# SS.net
KiCad netlist of a schematic drawn in Altium Designer
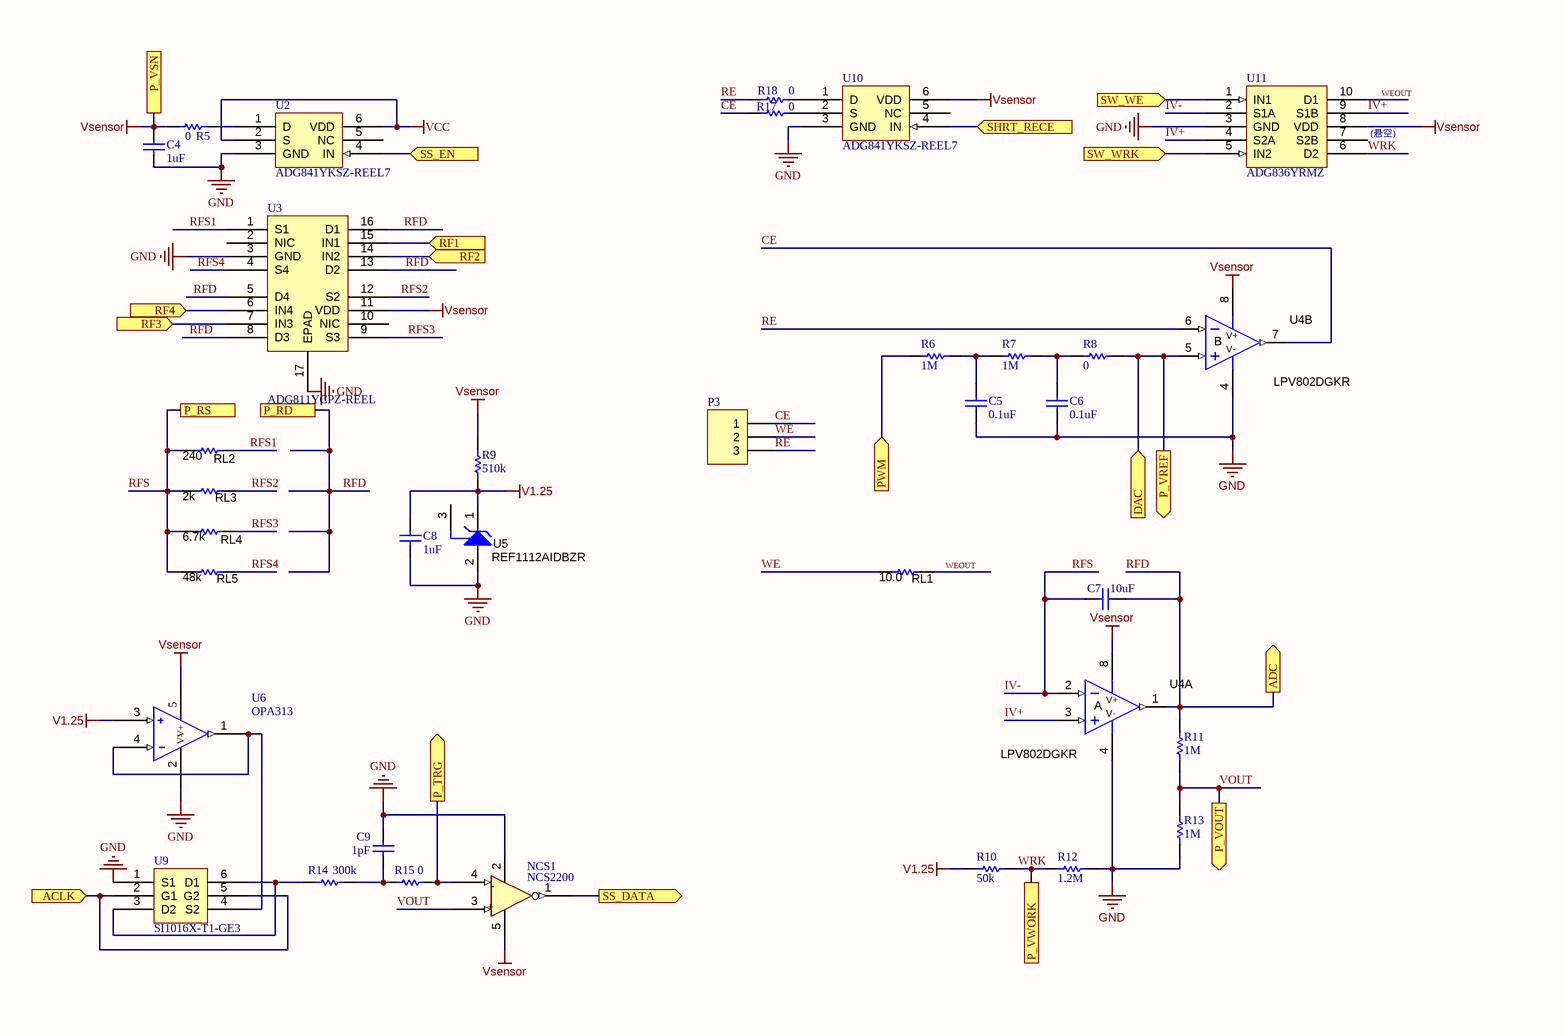
[diagram p0: SS.SchDoc]

(export (version "E")
  (design (tool "Eeschema 10.0.6"))
  (components
    (comp (ref "C4")
      (value "1uF")
      (footprint "0402")
      (description "Ceramic Capacitor (Surface Mount)")
      (fields (field (name "MANUFACTURER") "Generic Ceramic Chip Cap (TBD)"))
      (libsource (lib "Sensor") (part "Cap"))
    )
    (comp (ref "C5")
      (value "0.1uF")
      (footprint "0402")
      (description "Ceramic Capacitor (Surface Mount)")
      (fields (field (name "MANUFACTURER") "Generic Ceramic Chip Cap (TBD)"))
      (libsource (lib "Sensor") (part "Cap"))
    )
    (comp (ref "C6")
      (value "0.1uF")
      (footprint "0402")
      (description "Ceramic Capacitor (Surface Mount)")
      (fields (field (name "MANUFACTURER") "Generic Ceramic Chip Cap (TBD)"))
      (libsource (lib "Sensor") (part "Cap"))
    )
    (comp (ref "C7")
      (value "10uF")
      (footprint "0402")
      (description "Ceramic Capacitor (Surface Mount)")
      (fields (field (name "MANUFACTURER") "Generic Ceramic Chip Cap (TBD)"))
      (libsource (lib "Sensor") (part "Cap"))
    )
    (comp (ref "C8")
      (value "1uF")
      (footprint "0402")
      (description "Ceramic Capacitor (Surface Mount)")
      (fields (field (name "MANUFACTURER") "Generic Ceramic Chip Cap (TBD)"))
      (libsource (lib "Sensor") (part "Cap"))
    )
    (comp (ref "C9")
      (value "1pF")
      (footprint "0805")
      (description "Ceramic Capacitor (Surface Mount)")
      (fields (field (name "MANUFACTURER") "Generic Ceramic Chip Cap (TBD)"))
      (libsource (lib "Sensor") (part "Cap"))
    )
    (comp (ref "NCS1")
      (value "NCS2200")
      (footprint "SC70-5")
      (description "Comparator: On Semi 10uA Comparator")
      (fields
        (field (name "DIGI-KEY PART NUMBER") "NCS2200SQ2T2GOSTR-ND")
        (field (name "MANUFACTURER") "ON Semiconductor")
      )
      (libsource (lib "Sensor") (part "NCS2200"))
    )
    (comp (ref "P3")
      (value "~")
      (footprint "HDR1X3")
      (description "Header, 3-Pin")
      (fields (field (name "PUBLISHER") "Altium Limited"))
      (libsource (lib "Miscellaneous Connectors") (part "Header 3"))
    )
    (comp (ref "R5")
      (value "0")
      (footprint "0402")
      (description "Chip Resistor (Surface Mount)")
      (fields (field (name "MANUFACTURER") "Generic Chip Res (TBD)"))
      (libsource (lib "Sensor") (part "Res"))
    )
    (comp (ref "R6")
      (value "1M")
      (footprint "0402")
      (description "Chip Resistor (Surface Mount)")
      (fields (field (name "MANUFACTURER") "Generic Chip Res (TBD)"))
      (libsource (lib "Sensor") (part "Res"))
    )
    (comp (ref "R7")
      (value "1M")
      (footprint "0402")
      (description "Chip Resistor (Surface Mount)")
      (fields (field (name "MANUFACTURER") "Generic Chip Res (TBD)"))
      (libsource (lib "Sensor") (part "Res"))
    )
    (comp (ref "R8")
      (value "0")
      (footprint "0402")
      (description "Chip Resistor (Surface Mount)")
      (fields (field (name "MANUFACTURER") "Generic Chip Res (TBD)"))
      (libsource (lib "Sensor") (part "Res"))
    )
    (comp (ref "R9")
      (value "510k")
      (footprint "0402")
      (description "Chip Resistor (Surface Mount)")
      (fields (field (name "MANUFACTURER") "Generic Chip Res (TBD)"))
      (libsource (lib "Sensor") (part "Res"))
    )
    (comp (ref "R10")
      (value "50k")
      (footprint "0402")
      (description "Chip Resistor (Surface Mount)")
      (fields (field (name "MANUFACTURER") "Generic Chip Res (TBD)"))
      (libsource (lib "Sensor") (part "Res"))
    )
    (comp (ref "R11")
      (value "1M")
      (footprint "0402")
      (description "Chip Resistor (Surface Mount)")
      (fields (field (name "MANUFACTURER") "Generic Chip Res (TBD)"))
      (libsource (lib "Sensor") (part "Res"))
    )
    (comp (ref "R12")
      (value "1.2M")
      (footprint "0402")
      (description "Chip Resistor (Surface Mount)")
      (fields (field (name "MANUFACTURER") "Generic Chip Res (TBD)"))
      (libsource (lib "Sensor") (part "Res"))
    )
    (comp (ref "R13")
      (value "1M")
      (footprint "0402")
      (description "Chip Resistor (Surface Mount)")
      (fields (field (name "MANUFACTURER") "Generic Chip Res (TBD)"))
      (libsource (lib "Sensor") (part "Res"))
    )
    (comp (ref "R14")
      (value "300k")
      (footprint "0805")
      (description "Chip Resistor (Surface Mount)")
      (fields (field (name "MANUFACTURER") "Generic Chip Res (TBD)"))
      (libsource (lib "Sensor") (part "Res"))
    )
    (comp (ref "R15")
      (value "0")
      (footprint "0402")
      (description "Chip Resistor (Surface Mount)")
      (fields (field (name "MANUFACTURER") "Generic Chip Res (TBD)"))
      (libsource (lib "Sensor") (part "Res"))
    )
    (comp (ref "R17")
      (value "0")
      (footprint "0402")
      (description "Chip Resistor (Surface Mount)")
      (fields (field (name "MANUFACTURER") "Generic Chip Res (TBD)"))
      (libsource (lib "Sensor") (part "Res"))
    )
    (comp (ref "R18")
      (value "0")
      (footprint "0402")
      (description "Chip Resistor (Surface Mount)")
      (fields (field (name "MANUFACTURER") "Generic Chip Res (TBD)"))
      (libsource (lib "Sensor") (part "Res"))
    )
    (comp (ref "RL1")
      (value "10.0")
      (footprint "0402")
      (description "RES, 10.0, 0.1%, 0.1 W, 0402")
      (fields (field (name "Comment") "RT0402BRD0710RL"))
      (libsource (lib "Sensor") (part "RT0402BRD0710RL"))
    )
    (comp (ref "RL2")
      (value "240")
      (footprint "0402")
      (description "RES, 240, 0.1%, 0.1 W, 0402")
      (fields (field (name "Comment") "RT0402BRD07240RL"))
      (libsource (lib "Sensor") (part "RT0402BRD07240RL"))
    )
    (comp (ref "RL3")
      (value "2k")
      (footprint "0402")
      (description "RES, 2k, 0.1%, 0.1 W, 0402")
      (fields (field (name "Comment") "RT0402BRD072KL"))
      (libsource (lib "Sensor") (part "RT0402BRD072KL"))
    )
    (comp (ref "RL4")
      (value "6.7k")
      (footprint "0402")
      (description "RES, 6.7k, 0.1%, 0.1 W, 0402")
      (fields (field (name "Comment") "RT0402BRD076K7L"))
      (libsource (lib "Sensor") (part "RT0402BRD076K7L"))
    )
    (comp (ref "RL5")
      (value "48k")
      (footprint "0402")
      (description "RES, 48k, 0.1%, 0.1 W, 0402")
      (fields (field (name "Comment") "RT0402BRD0748KL"))
      (libsource (lib "Sensor") (part "RT0402BRD0748KL"))
    )
    (comp (ref "U2")
      (value "ADG841YKSZ-REEL7")
      (footprint "SOT65P210X110-6N")
      (description "单通道单刀单掷开关")
      (libsource (lib "Sensor") (part "ADG841YKSZ-REEL7"))
    )
    (comp (ref "U3")
      (value "ADG811YCPZ-REEL")
      (footprint "QFN50P300X300X90-17N")
      (description "四通道单刀单掷开关")
      (libsource (lib "9e10b744bb4c87c33691f54f9cb3eff1_25b2db50bc18869c33ddf303d90bd74c_8") (part "ADG811YCPZ-REEL"))
    )
    (comp (ref "U4")
      (value "LPV802DGKR")
      (footprint "DGK0008A_N")
      (description "350 nA Rail-to-Rail I/O Nanopower Operational Amplifier Family, DGK0008A")
      (fields
        (field (name "ALTERNATE PARTNUMBER") "LPV802DGKT")
        (field (name "MANUFACTURER") "Texas Instruments")
        (field (name "PUBLISHER") "Texas Instruments")
      )
      (libsource (lib "Sensor") (part "LPV802DGKR"))
    )
    (comp (ref "U5")
      (value "REF1112AIDBZR")
      (footprint "DBZ0003A_N")
      (fields
        (field (name "MANUFACTURER") "Texas Instruments")
        (field (name "ALTERNATE PARTNUMBER") "Equivalent")
      )
      (libsource (lib "Sensor") (part "REF1112AIDBZR"))
    )
    (comp (ref "U6")
      (value "OPA313")
      (footprint "SOT95P280X145-5N")
      (description "低功耗运算放大器")
      (libsource (lib "Sensor") (part "OPA313"))
    )
    (comp (ref "U9")
      (value "SI1016X-T1-GE3")
      (footprint "SC-89-6 Vishay")
      (description "N/P沟道增强型MOS管")
      (libsource (lib "Sensor") (part "SI1016X-T1-GE3"))
    )
    (comp (ref "U10")
      (value "ADG841YKSZ-REEL7")
      (footprint "SOT65P210X110-6N")
      (description "单通道单刀单掷开关")
      (libsource (lib "Sensor") (part "ADG841YKSZ-REEL7"))
    )
    (comp (ref "U11")
      (value "ADG836YRMZ")
      (footprint "SOP50P490X110-10N")
      (description "双通道单刀双掷开关")
      (libsource (lib "Sensor") (part "ADG836YRMZ"))
    )
  )
  (nets
    (net (code "2") (name "/ACLK") (class "Default")
      (node (ref "U9") (pin "2") (pinfunction "G1_2") (pintype "passive"))
      (node (ref "U9") (pin "5") (pinfunction "G2_5") (pintype "passive"))
    )
    (net (code "3") (name "/CE") (class "Default")
      (node (ref "P3") (pin "1") (pinfunction "1_1") (pintype "passive"))
      (node (ref "R17") (pin "2") (pinfunction "2_2") (pintype "passive"))
      (node (ref "U4") (pin "7") (pinfunction "OUT_7") (pintype "output"))
    )
    (net (code "4") (name "/DAC") (class "Default")
      (node (ref "R8") (pin "2") (pinfunction "2_2") (pintype "passive"))
      (node (ref "U4") (pin "5") (pinfunction "IN+_5") (pintype "input"))
    )
    (net (code "5") (name "/IV+") (class "Default")
      (node (ref "U11") (pin "4") (pinfunction "S2A_4") (pintype "passive"))
      (node (ref "U11") (pin "9") (pinfunction "S1B_9") (pintype "passive"))
      (node (ref "U4") (pin "3") (pinfunction "IN+_3") (pintype "input"))
    )
    (net (code "6") (name "/IV-") (class "Default")
      (node (ref "C7") (pin "2") (pinfunction "2_2") (pintype "passive"))
      (node (ref "RL2") (pin "1") (pinfunction "1_1") (pintype "passive"))
      (node (ref "RL3") (pin "1") (pinfunction "1_1") (pintype "passive"))
      (node (ref "RL4") (pin "1") (pinfunction "1_1") (pintype "passive"))
      (node (ref "RL5") (pin "1") (pinfunction "1_1") (pintype "passive"))
      (node (ref "U11") (pin "2") (pinfunction "S1A_2") (pintype "passive"))
      (node (ref "U4") (pin "2") (pinfunction "IN-_2") (pintype "input"))
    )
    (net (code "7") (name "/PWM") (class "Default")
      (node (ref "R6") (pin "2") (pinfunction "2_2") (pintype "passive"))
    )
    (net (code "8") (name "/P_TRG") (class "Default")
      (node (ref "NCS1") (pin "4") (pinfunction "In-_4") (pintype "input"))
      (node (ref "R15") (pin "1") (pinfunction "1_1") (pintype "passive"))
    )
    (net (code "9") (name "/RE") (class "Default")
      (node (ref "P3") (pin "3") (pinfunction "3_3") (pintype "passive"))
      (node (ref "R18") (pin "2") (pinfunction "2_2") (pintype "passive"))
      (node (ref "U4") (pin "6") (pinfunction "IN-_6") (pintype "input"))
    )
    (net (code "10") (name "/RF1") (class "Default")
      (node (ref "U3") (pin "15") (pinfunction "IN1_15") (pintype "passive"))
    )
    (net (code "11") (name "/RF2") (class "Default")
      (node (ref "U3") (pin "14") (pinfunction "IN2_14") (pintype "passive"))
    )
    (net (code "12") (name "/RF3") (class "Default")
      (node (ref "U3") (pin "7") (pinfunction "IN3_7") (pintype "passive"))
    )
    (net (code "13") (name "/RF4") (class "Default")
      (node (ref "U3") (pin "6") (pinfunction "IN4_6") (pintype "passive"))
    )
    (net (code "14") (name "/RFD") (class "Default")
      (node (ref "C7") (pin "1") (pinfunction "1_1") (pintype "passive"))
      (node (ref "R11") (pin "1") (pinfunction "1_1") (pintype "passive"))
      (node (ref "U3") (pin "13") (pinfunction "D2_13") (pintype "passive"))
      (node (ref "U3") (pin "16") (pinfunction "D1_16") (pintype "passive"))
      (node (ref "U3") (pin "5") (pinfunction "D4_5") (pintype "passive"))
      (node (ref "U3") (pin "8") (pinfunction "D3_8") (pintype "passive"))
      (node (ref "U4") (pin "1") (pinfunction "OUT_1") (pintype "output"))
    )
    (net (code "15") (name "/RFS1") (class "Default")
      (node (ref "RL2") (pin "2") (pinfunction "2_2") (pintype "passive"))
      (node (ref "U3") (pin "1") (pinfunction "S1_1") (pintype "passive"))
    )
    (net (code "16") (name "/RFS2") (class "Default")
      (node (ref "RL3") (pin "2") (pinfunction "2_2") (pintype "passive"))
      (node (ref "U3") (pin "12") (pinfunction "S2_12") (pintype "passive"))
    )
    (net (code "17") (name "/RFS3") (class "Default")
      (node (ref "RL4") (pin "2") (pinfunction "2_2") (pintype "passive"))
      (node (ref "U3") (pin "9") (pinfunction "S3_9") (pintype "passive"))
    )
    (net (code "18") (name "/RFS4") (class "Default")
      (node (ref "RL5") (pin "2") (pinfunction "2_2") (pintype "passive"))
      (node (ref "U3") (pin "4") (pinfunction "S4_4") (pintype "passive"))
    )
    (net (code "19") (name "/SHRT_RECE") (class "Default")
      (node (ref "U10") (pin "4") (pinfunction "IN_4") (pintype "input"))
    )
    (net (code "20") (name "/SS_DATA") (class "Default")
      (node (ref "NCS1") (pin "1") (pinfunction "OUT_1") (pintype "output"))
    )
    (net (code "21") (name "/SS_EN") (class "Default")
      (node (ref "U2") (pin "4") (pinfunction "IN_4") (pintype "input"))
    )
    (net (code "22") (name "/SW_WE") (class "Default")
      (node (ref "U11") (pin "1") (pinfunction "IN1_1") (pintype "input"))
    )
    (net (code "23") (name "/SW_WRK") (class "Default")
      (node (ref "U11") (pin "5") (pinfunction "IN2_5") (pintype "input"))
    )
    (net (code "24") (name "/VOUT") (class "Default")
      (node (ref "NCS1") (pin "3") (pinfunction "IN+_3") (pintype "input"))
      (node (ref "R11") (pin "2") (pinfunction "2_2") (pintype "passive"))
      (node (ref "R13") (pin "1") (pinfunction "1_1") (pintype "passive"))
    )
    (net (code "25") (name "/WE") (class "Default")
      (node (ref "P3") (pin "2") (pinfunction "2_2") (pintype "passive"))
      (node (ref "RL1") (pin "1") (pinfunction "1_1") (pintype "passive"))
    )
    (net (code "26") (name "/WEOUT") (class "Default")
      (node (ref "RL1") (pin "2") (pinfunction "2_2") (pintype "passive"))
      (node (ref "U11") (pin "10") (pinfunction "D1_10") (pintype "passive"))
    )
    (net (code "27") (name "/WRK") (class "Default")
      (node (ref "R10") (pin "2") (pinfunction "2_2") (pintype "passive"))
      (node (ref "R12") (pin "1") (pinfunction "1_1") (pintype "passive"))
      (node (ref "U11") (pin "6") (pinfunction "D2_6") (pintype "passive"))
    )
    (net (code "28") (name "GND") (class "Default")
      (node (ref "C4") (pin "2") (pinfunction "2_2") (pintype "passive"))
      (node (ref "C5") (pin "2") (pinfunction "2_2") (pintype "passive"))
      (node (ref "C6") (pin "1") (pinfunction "1_1") (pintype "passive"))
      (node (ref "C8") (pin "1") (pinfunction "1_1") (pintype "passive"))
      (node (ref "C9") (pin "1") (pinfunction "1_1") (pintype "passive"))
      (node (ref "NCS1") (pin "2") (pinfunction "GND_2") (pintype "power_in"))
      (node (ref "R12") (pin "2") (pinfunction "2_2") (pintype "passive"))
      (node (ref "R13") (pin "2") (pinfunction "2_2") (pintype "passive"))
      (node (ref "U10") (pin "3") (pinfunction "GND_3") (pintype "power_in"))
      (node (ref "U11") (pin "3") (pinfunction "GND_3") (pintype "power_in"))
      (node (ref "U2") (pin "3") (pinfunction "GND_3") (pintype "power_in"))
      (node (ref "U3") (pin "17") (pinfunction "EPAD_17") (pintype "passive"))
      (node (ref "U3") (pin "3") (pinfunction "GND_3") (pintype "passive"))
      (node (ref "U4") (pin "4") (pinfunction "V-_4") (pintype "power_in"))
      (node (ref "U5") (pin "2") (pinfunction "GND_2") (pintype "power_in"))
      (node (ref "U6") (pin "2") (pinfunction "V-_2") (pintype "power_in"))
      (node (ref "U9") (pin "1") (pinfunction "S1_1") (pintype "passive"))
    )
    (net (code "29") (name "Net-(C5-Pad1)") (class "Default")
      (node (ref "C5") (pin "1") (pinfunction "1_1") (pintype "passive"))
      (node (ref "R6") (pin "1") (pinfunction "1_1") (pintype "passive"))
      (node (ref "R7") (pin "2") (pinfunction "2_2") (pintype "passive"))
    )
    (net (code "30") (name "Net-(C6-Pad2)") (class "Default")
      (node (ref "C6") (pin "2") (pinfunction "2_2") (pintype "passive"))
      (node (ref "R7") (pin "1") (pinfunction "1_1") (pintype "passive"))
      (node (ref "R8") (pin "1") (pinfunction "1_1") (pintype "passive"))
    )
    (net (code "31") (name "Net-(C9-Pad2)") (class "Default")
      (node (ref "C9") (pin "2") (pinfunction "2_2") (pintype "passive"))
      (node (ref "R14") (pin "1") (pinfunction "1_1") (pintype "passive"))
      (node (ref "R15") (pin "2") (pinfunction "2_2") (pintype "passive"))
    )
    (net (code "32") (name "Net-(U2-D)") (class "Default")
      (node (ref "R5") (pin "2") (pinfunction "2_2") (pintype "passive"))
      (node (ref "U2") (pin "1") (pinfunction "D_1") (pintype "passive"))
    )
    (net (code "33") (name "Net-(U9-D1)") (class "Default")
      (node (ref "R14") (pin "2") (pinfunction "2_2") (pintype "passive"))
      (node (ref "U9") (pin "3") (pinfunction "D2_3") (pintype "power_in"))
      (node (ref "U9") (pin "6") (pinfunction "D1_6") (pintype "power_in"))
    )
    (net (code "34") (name "Net-(U9-S2)") (class "Default")
      (node (ref "U6") (pin "1") (pintype "output"))
      (node (ref "U6") (pin "4") (pintype "input"))
      (node (ref "U9") (pin "4") (pinfunction "S2_4") (pintype "passive"))
    )
    (net (code "35") (name "Net-(U10-D)") (class "Default")
      (node (ref "R18") (pin "1") (pinfunction "1_1") (pintype "passive"))
      (node (ref "U10") (pin "1") (pinfunction "D_1") (pintype "passive"))
    )
    (net (code "36") (name "Net-(U10-S)") (class "Default")
      (node (ref "R17") (pin "1") (pinfunction "1_1") (pintype "passive"))
      (node (ref "U10") (pin "2") (pinfunction "S_2") (pintype "passive"))
    )
    (net (code "37") (name "V1.25") (class "Default")
      (node (ref "C8") (pin "2") (pinfunction "2_2") (pintype "passive"))
      (node (ref "R10") (pin "1") (pinfunction "1_1") (pintype "passive"))
      (node (ref "R9") (pin "1") (pinfunction "1_1") (pintype "passive"))
      (node (ref "U5") (pin "1") (pinfunction "VO_1") (pintype "passive"))
      (node (ref "U6") (pin "3") (pintype "input"))
    )
    (net (code "38") (name "VCC") (class "Default")
      (node (ref "U2") (pin "2") (pinfunction "S_2") (pintype "passive"))
      (node (ref "U2") (pin "6") (pinfunction "VDD_6") (pintype "power_in"))
    )
    (net (code "39") (name "Vsensor") (class "Default")
      (node (ref "C4") (pin "1") (pinfunction "1_1") (pintype "passive"))
      (node (ref "NCS1") (pin "5") (pinfunction "VDD_5") (pintype "power_in"))
      (node (ref "R5") (pin "1") (pinfunction "1_1") (pintype "passive"))
      (node (ref "R9") (pin "2") (pinfunction "2_2") (pintype "passive"))
      (node (ref "U10") (pin "6") (pinfunction "VDD_6") (pintype "power_in"))
      (node (ref "U11") (pin "8") (pinfunction "VDD_8") (pintype "power_in"))
      (node (ref "U3") (pin "11") (pinfunction "VDD_11") (pintype "passive"))
      (node (ref "U4") (pin "8") (pinfunction "V+_8") (pintype "power_in"))
      (node (ref "U6") (pin "5") (pinfunction "V+_5") (pintype "power_in"))
    )
    (net (code "40") (name "unconnected-(U2-NC-Pad5)") (class "Default")
      (node (ref "U2") (pin "5") (pinfunction "NC_5") (pintype "passive"))
    )
    (net (code "41") (name "unconnected-(U3-NIC-Pad2)") (class "Default")
      (node (ref "U3") (pin "2") (pinfunction "NIC_2") (pintype "passive"))
    )
    (net (code "42") (name "unconnected-(U3-NIC-Pad10)") (class "Default")
      (node (ref "U3") (pin "10") (pinfunction "NIC_10") (pintype "passive"))
    )
    (net (code "43") (name "unconnected-(U5-NC-Pad3)") (class "Default")
      (node (ref "U5") (pin "3") (pinfunction "NC_3") (pintype "passive"))
    )
    (net (code "44") (name "unconnected-(U10-NC-Pad5)") (class "Default")
      (node (ref "U10") (pin "5") (pinfunction "NC_5") (pintype "passive"))
    )
    (net (code "45") (name "unconnected-(U11-S2B-Pad7)") (class "Default")
      (node (ref "U11") (pin "7") (pinfunction "S2B_7") (pintype "passive"))
    )
  )
)
